# LTC_Hardware.net
KiCad netlist of a schematic drawn in Altium Designer
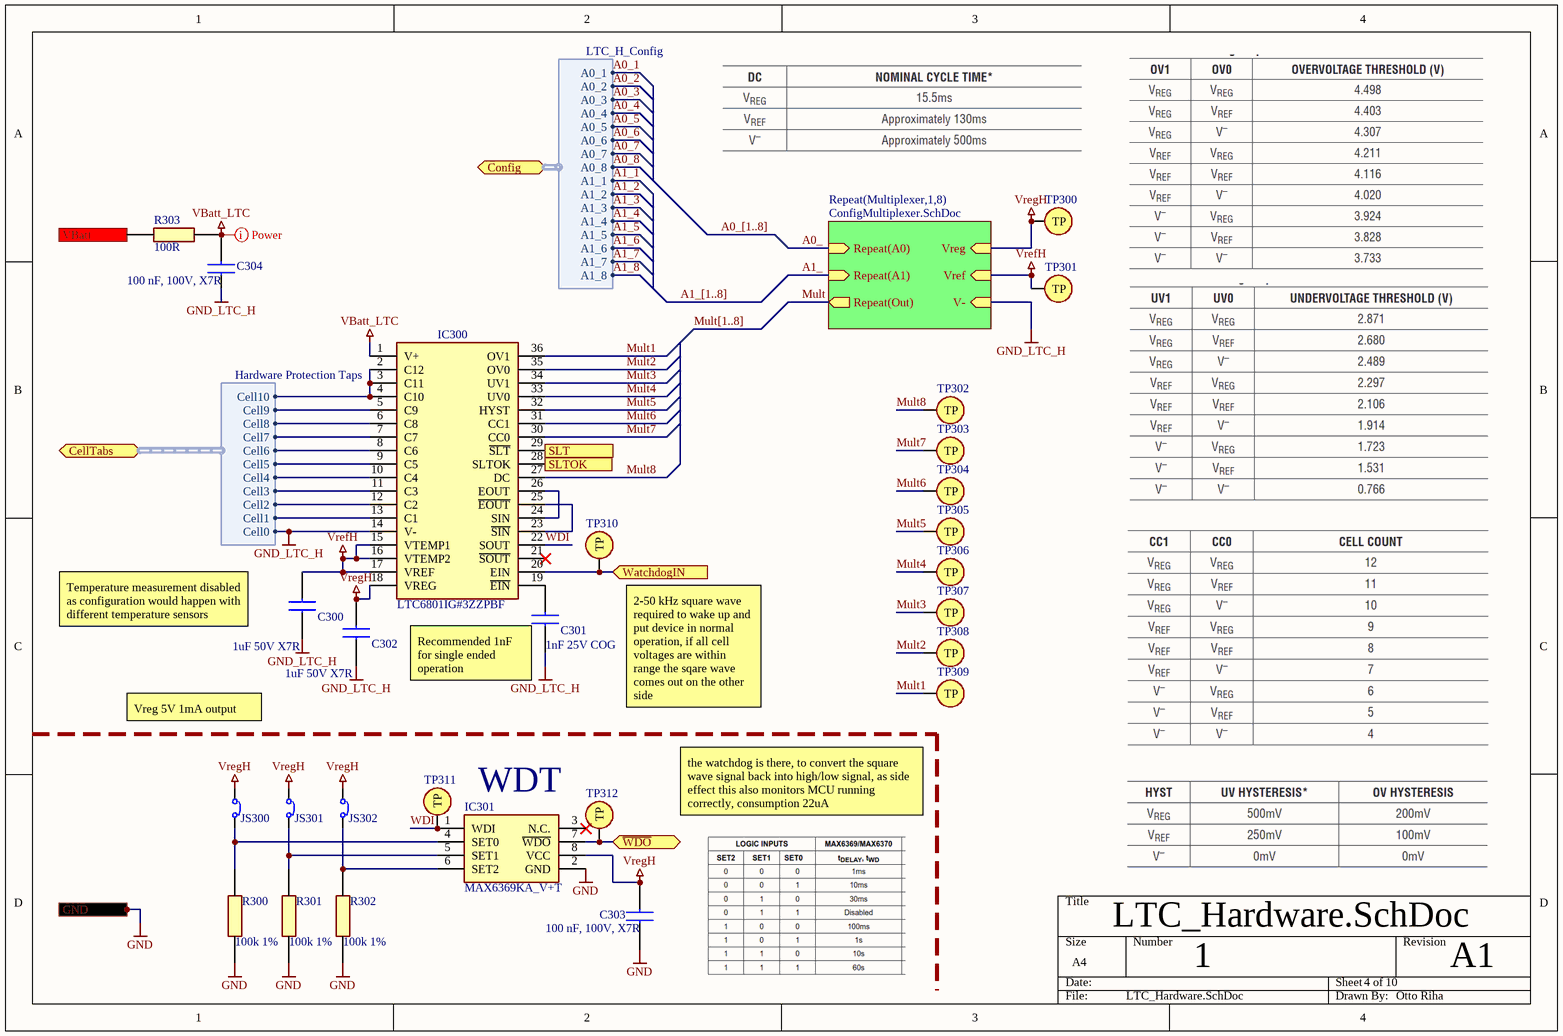
[diagram p0: LTC_Hardware.SchDoc]

(export (version "E")
  (design (tool "Eeschema 10.0.6"))
  (components
    (comp (ref "C300")
      (value "1uF 50V X7R")
      (footprint "SamacSys:CAPC1608X90N")
      (description "Capacitor 1uF 50V X7R")
      (fields
        (field (name "MANUFACTURER_PART_NUMBER") "06035C105MAT2A")
        (field (name "MOUSER PART NUMBER") "581-06035C105MAT2A")
      )
      (libsource (lib "SamacSys") (part "06035C105MAT2A"))
    )
    (comp (ref "C301")
      (value "1nF 25V COG")
      (footprint "SamacSys:CAPC1608X90N")
      (description "Capacitor 1nF 25V COG")
      (fields
        (field (name "MANUFACTURER_PART_NUMBER") "06033A102FAT2A")
        (field (name "MOUSER PART NUMBER") "581-06033A102F")
      )
      (libsource (lib "SamacSys") (part "06033A102FAT2A"))
    )
    (comp (ref "C302")
      (value "1uF 50V X7R")
      (footprint "SamacSys:CAPC1608X90N")
      (description "Capacitor 1uF 50V X7R")
      (fields
        (field (name "MANUFACTURER_PART_NUMBER") "06035C105MAT2A")
        (field (name "MOUSER PART NUMBER") "581-06035C105MAT2A")
      )
      (libsource (lib "SamacSys") (part "06035C105MAT2A"))
    )
    (comp (ref "C303")
      (value "100 nF, 100V, X7R")
      (footprint "SamacSys:MAJx16")
      (description "Capacitor 100nF, 100V, X7R")
      (fields
        (field (name "MANUFACTURER_PART_NUMBER") "MAJCH168BB7104KTEA01")
        (field (name "MOUSER PART NUMBER") "963-MAJCH168BB7104KT")
      )
      (libsource (lib "SamacSys") (part "MAJCH168BB7104KTEA01"))
    )
    (comp (ref "C304")
      (value "100 nF, 100V, X7R")
      (footprint "SamacSys:MAJx16")
      (description "Capacitor 100nF, 100V, X7R")
      (fields
        (field (name "MANUFACTURER_PART_NUMBER") "MAJCH168BB7104KTEA01")
        (field (name "MOUSER PART NUMBER") "963-MAJCH168BB7104KT")
      )
      (libsource (lib "SamacSys") (part "MAJCH168BB7104KTEA01"))
    )
    (comp (ref "IC300")
      (value "LTC6801IG#3ZZPBF")
      (footprint "SamacSys:SOP65P780X200-36N")
      (description "Integrated Circuit")
      (fields (field (name "MOUSER PART NUMBER") "584-LTC6801IG#3ZZPBF"))
      (libsource (lib "*") (part "LTC6801IG#3ZZPBF"))
    )
    (comp (ref "IC301")
      (value "MAX6369KA_V+T")
      (footprint "SamacSys:SOT65P280X145-8N")
      (description "Integrated Circuit")
      (fields
        (field (name "MANUFACTURER_PART_NUMBER") "MAX6369KA/V+T")
        (field (name "MOUSER PART NUMBER") "700-MAX6369KA/V+T")
      )
      (libsource (lib "SamacSys") (part "MAX6369KA_V+T"))
    )
    (comp (ref "JS300")
      (value "SolderJumper")
      (footprint "SolderJumper")
      (libsource (lib "SamacSys") (part "SolderJumper"))
    )
    (comp (ref "JS301")
      (value "SolderJumper")
      (footprint "SolderJumper")
      (libsource (lib "SamacSys") (part "SolderJumper"))
    )
    (comp (ref "JS302")
      (value "SolderJumper")
      (footprint "SolderJumper")
      (libsource (lib "SamacSys") (part "SolderJumper"))
    )
    (comp (ref "R300")
      (value "100k 1%")
      (footprint "SamacSys:RESC1608X55N")
      (description "Resistor 100k, 1%")
      (fields
        (field (name "MANUFACTURER_PART_NUMBER") "CRCW0603100KFKEAC")
        (field (name "MOUSER PART NUMBER") "71-CRCW0603100KFKEAC")
      )
      (libsource (lib "SamacSys") (part "CRCW0603100KFKEAC"))
    )
    (comp (ref "R301")
      (value "100k 1%")
      (footprint "SamacSys:RESC1608X55N")
      (description "Resistor 100k, 1%")
      (fields
        (field (name "MANUFACTURER_PART_NUMBER") "CRCW0603100KFKEAC")
        (field (name "MOUSER PART NUMBER") "71-CRCW0603100KFKEAC")
      )
      (libsource (lib "SamacSys") (part "CRCW0603100KFKEAC"))
    )
    (comp (ref "R302")
      (value "100k 1%")
      (footprint "SamacSys:RESC1608X55N")
      (description "Resistor 100k, 1%")
      (fields
        (field (name "MANUFACTURER_PART_NUMBER") "CRCW0603100KFKEAC")
        (field (name "MOUSER PART NUMBER") "71-CRCW0603100KFKEAC")
      )
      (libsource (lib "SamacSys") (part "CRCW0603100KFKEAC"))
    )
    (comp (ref "R303")
      (value "100R")
      (footprint "SamacSys:RESC1608X50N")
      (description "Resistor 100R, 1%")
      (fields
        (field (name "MANUFACTURER_PART_NUMBER") "CRCW0603100RFKEA")
        (field (name "MOUSER PART NUMBER") "71-CRCW0603-100-E3")
      )
      (libsource (lib "SamacSys") (part "CRCW0603100RFKEA"))
    )
    (comp (ref "TP300")
      (value "Testpoint")
      (footprint "Testpoint")
      (libsource (lib "SamacSys") (part "Testpoint"))
    )
    (comp (ref "TP301")
      (value "Testpoint")
      (footprint "Testpoint")
      (libsource (lib "SamacSys") (part "Testpoint"))
    )
    (comp (ref "TP302")
      (value "Testpoint")
      (footprint "Testpoint")
      (libsource (lib "SamacSys") (part "Testpoint"))
    )
    (comp (ref "TP303")
      (value "Testpoint")
      (footprint "Testpoint")
      (libsource (lib "SamacSys") (part "Testpoint"))
    )
    (comp (ref "TP304")
      (value "Testpoint")
      (footprint "Testpoint")
      (libsource (lib "SamacSys") (part "Testpoint"))
    )
    (comp (ref "TP305")
      (value "Testpoint")
      (footprint "Testpoint")
      (libsource (lib "SamacSys") (part "Testpoint"))
    )
    (comp (ref "TP306")
      (value "Testpoint")
      (footprint "Testpoint")
      (libsource (lib "SamacSys") (part "Testpoint"))
    )
    (comp (ref "TP307")
      (value "Testpoint")
      (footprint "Testpoint")
      (libsource (lib "SamacSys") (part "Testpoint"))
    )
    (comp (ref "TP308")
      (value "Testpoint")
      (footprint "Testpoint")
      (libsource (lib "SamacSys") (part "Testpoint"))
    )
    (comp (ref "TP309")
      (value "Testpoint")
      (footprint "Testpoint")
      (libsource (lib "SamacSys") (part "Testpoint"))
    )
    (comp (ref "TP310")
      (value "Testpoint")
      (footprint "Testpoint")
      (libsource (lib "SamacSys") (part "Testpoint"))
    )
    (comp (ref "TP311")
      (value "Testpoint")
      (footprint "Testpoint")
      (libsource (lib "SamacSys") (part "Testpoint"))
    )
    (comp (ref "TP312")
      (value "Testpoint")
      (footprint "Testpoint")
      (libsource (lib "SamacSys") (part "Testpoint"))
    )
  )
  (nets
    (net (code "25") (name "/Cell1") (class "Default")
      (node (ref "IC300") (pin "13") (pinfunction "C1_13") (pintype "passive"))
    )
    (net (code "26") (name "/Cell2") (class "Default")
      (node (ref "IC300") (pin "12") (pinfunction "C2_12") (pintype "passive"))
    )
    (net (code "27") (name "/Cell3") (class "Default")
      (node (ref "IC300") (pin "11") (pinfunction "C3_11") (pintype "passive"))
    )
    (net (code "28") (name "/Cell4") (class "Default")
      (node (ref "IC300") (pin "10") (pinfunction "C4_10") (pintype "passive"))
    )
    (net (code "29") (name "/Cell5") (class "Default")
      (node (ref "IC300") (pin "9") (pinfunction "C5_9") (pintype "passive"))
    )
    (net (code "30") (name "/Cell6") (class "Default")
      (node (ref "IC300") (pin "8") (pinfunction "C6_8") (pintype "passive"))
    )
    (net (code "31") (name "/Cell7") (class "Default")
      (node (ref "IC300") (pin "7") (pinfunction "C7_7") (pintype "passive"))
    )
    (net (code "32") (name "/Cell8") (class "Default")
      (node (ref "IC300") (pin "6") (pinfunction "C8_6") (pintype "passive"))
    )
    (net (code "33") (name "/Cell9") (class "Default")
      (node (ref "IC300") (pin "5") (pinfunction "C9_5") (pintype "passive"))
    )
    (net (code "34") (name "/Cell10") (class "Default")
      (node (ref "IC300") (pin "2") (pinfunction "C12_2") (pintype "passive"))
      (node (ref "IC300") (pin "3") (pinfunction "C11_3") (pintype "passive"))
      (node (ref "IC300") (pin "4") (pinfunction "C10_4") (pintype "passive"))
    )
    (net (code "36") (name "/Mult1") (class "Default")
      (node (ref "IC300") (pin "36") (pinfunction "OV1_36") (pintype "passive"))
      (node (ref "TP309") (pin "1") (pinfunction "TP_1") (pintype "passive"))
    )
    (net (code "37") (name "/Mult2") (class "Default")
      (node (ref "IC300") (pin "35") (pinfunction "OV0_35") (pintype "passive"))
      (node (ref "TP308") (pin "1") (pinfunction "TP_1") (pintype "passive"))
    )
    (net (code "38") (name "/Mult3") (class "Default")
      (node (ref "IC300") (pin "34") (pinfunction "UV1_34") (pintype "passive"))
      (node (ref "TP307") (pin "1") (pinfunction "TP_1") (pintype "passive"))
    )
    (net (code "39") (name "/Mult4") (class "Default")
      (node (ref "IC300") (pin "33") (pinfunction "UV0_33") (pintype "passive"))
      (node (ref "TP306") (pin "1") (pinfunction "TP_1") (pintype "passive"))
    )
    (net (code "40") (name "/Mult5") (class "Default")
      (node (ref "IC300") (pin "32") (pinfunction "HYST_32") (pintype "passive"))
      (node (ref "TP305") (pin "1") (pinfunction "TP_1") (pintype "passive"))
    )
    (net (code "41") (name "/Mult6") (class "Default")
      (node (ref "IC300") (pin "31") (pinfunction "CC1_31") (pintype "passive"))
      (node (ref "TP304") (pin "1") (pinfunction "TP_1") (pintype "passive"))
    )
    (net (code "42") (name "/Mult7") (class "Default")
      (node (ref "IC300") (pin "30") (pinfunction "CC0_30") (pintype "passive"))
      (node (ref "TP303") (pin "1") (pinfunction "TP_1") (pintype "passive"))
    )
    (net (code "43") (name "/Mult8") (class "Default")
      (node (ref "IC300") (pin "27") (pinfunction "DC_27") (pintype "passive"))
      (node (ref "TP302") (pin "1") (pinfunction "TP_1") (pintype "passive"))
    )
    (net (code "45") (name "/SLT") (class "Default")
      (node (ref "IC300") (pin "29") (pinfunction "~{SLT}_29") (pintype "passive"))
    )
    (net (code "46") (name "/SLTOK") (class "Default")
      (node (ref "IC300") (pin "28") (pinfunction "SLTOK_28") (pintype "passive"))
    )
    (net (code "47") (name "/VBatt") (class "Default")
      (node (ref "R303") (pin "1") (pinfunction "1_1") (pintype "passive"))
    )
    (net (code "48") (name "/WDI") (class "Default")
      (node (ref "IC300") (pin "22") (pinfunction "SOUT_22") (pintype "passive"))
      (node (ref "IC301") (pin "1") (pinfunction "WDI_1") (pintype "passive"))
      (node (ref "TP311") (pin "1") (pinfunction "TP_1") (pintype "passive"))
    )
    (net (code "49") (name "/WatchdogIN") (class "Default")
      (node (ref "IC300") (pin "20") (pinfunction "EIN_20") (pintype "passive"))
      (node (ref "TP310") (pin "1") (pinfunction "TP_1") (pintype "passive"))
    )
    (net (code "52") (name "/~{WDO}") (class "Default")
      (node (ref "IC301") (pin "7") (pinfunction "~{WDO}_7") (pintype "passive"))
      (node (ref "TP312") (pin "1") (pinfunction "TP_1") (pintype "passive"))
    )
    (net (code "53") (name "GND") (class "Default")
      (node (ref "C303") (pin "1") (pinfunction "1_1") (pintype "passive"))
      (node (ref "IC301") (pin "2") (pinfunction "GND_2") (pintype "power_in"))
      (node (ref "R300") (pin "1") (pinfunction "1_1") (pintype "passive"))
      (node (ref "R301") (pin "1") (pinfunction "1_1") (pintype "passive"))
      (node (ref "R302") (pin "1") (pinfunction "1_1") (pintype "passive"))
    )
    (net (code "54") (name "GND_LTC_H") (class "Default")
      (node (ref "C300") (pin "2") (pinfunction "2_2") (pintype "passive"))
      (node (ref "C301") (pin "1") (pinfunction "1_1") (pintype "passive"))
      (node (ref "C302") (pin "2") (pinfunction "2_2") (pintype "passive"))
      (node (ref "C304") (pin "1") (pinfunction "1_1") (pintype "passive"))
      (node (ref "IC300") (pin "14") (pinfunction "V-_14") (pintype "passive"))
    )
    (net (code "55") (name "Net-(IC300-EOUT)") (class "Default")
      (node (ref "IC300") (pin "24") (pinfunction "SIN_24") (pintype "passive"))
      (node (ref "IC300") (pin "26") (pinfunction "EOUT_26") (pintype "passive"))
    )
    (net (code "56") (name "Net-(IC300-~{EIN})") (class "Default")
      (node (ref "C301") (pin "2") (pinfunction "2_2") (pintype "passive"))
      (node (ref "IC300") (pin "19") (pinfunction "~{EIN}_19") (pintype "passive"))
    )
    (net (code "57") (name "Net-(IC300-~{EOUT})") (class "Default")
      (node (ref "IC300") (pin "23") (pinfunction "~{SIN}_23") (pintype "passive"))
      (node (ref "IC300") (pin "25") (pinfunction "~{EOUT}_25") (pintype "passive"))
    )
    (net (code "58") (name "Net-(IC301-SET0)") (class "Default")
      (node (ref "IC301") (pin "4") (pinfunction "SET0_4") (pintype "passive"))
      (node (ref "JS300") (pin "1") (pinfunction "1_1") (pintype "passive"))
      (node (ref "R300") (pin "2") (pinfunction "2_2") (pintype "passive"))
    )
    (net (code "59") (name "Net-(IC301-SET1)") (class "Default")
      (node (ref "IC301") (pin "5") (pinfunction "SET1_5") (pintype "passive"))
      (node (ref "JS301") (pin "1") (pinfunction "1_1") (pintype "passive"))
      (node (ref "R301") (pin "2") (pinfunction "2_2") (pintype "passive"))
    )
    (net (code "60") (name "Net-(IC301-SET2)") (class "Default")
      (node (ref "IC301") (pin "6") (pinfunction "SET2_6") (pintype "passive"))
      (node (ref "JS302") (pin "1") (pinfunction "1_1") (pintype "passive"))
      (node (ref "R302") (pin "2") (pinfunction "2_2") (pintype "passive"))
    )
    (net (code "61") (name "VBatt_LTC") (class "Default")
      (node (ref "C304") (pin "2") (pinfunction "2_2") (pintype "passive"))
      (node (ref "IC300") (pin "1") (pinfunction "V+_1") (pintype "passive"))
      (node (ref "R303") (pin "2") (pinfunction "2_2") (pintype "passive"))
    )
    (net (code "62") (name "VrefH") (class "Default")
      (node (ref "C300") (pin "1") (pinfunction "1_1") (pintype "passive"))
      (node (ref "IC300") (pin "15") (pinfunction "VTEMP1_15") (pintype "passive"))
      (node (ref "IC300") (pin "16") (pinfunction "VTEMP2_16") (pintype "passive"))
      (node (ref "IC300") (pin "17") (pinfunction "VREF_17") (pintype "passive"))
      (node (ref "TP301") (pin "1") (pinfunction "TP_1") (pintype "passive"))
    )
    (net (code "63") (name "VregH") (class "Default")
      (node (ref "C302") (pin "1") (pinfunction "1_1") (pintype "passive"))
      (node (ref "C303") (pin "2") (pinfunction "2_2") (pintype "passive"))
      (node (ref "IC300") (pin "18") (pinfunction "VREG_18") (pintype "passive"))
      (node (ref "IC301") (pin "8") (pinfunction "VCC_8") (pintype "power_in"))
      (node (ref "JS300") (pin "2") (pinfunction "2_2") (pintype "passive"))
      (node (ref "JS301") (pin "2") (pinfunction "2_2") (pintype "passive"))
      (node (ref "JS302") (pin "2") (pinfunction "2_2") (pintype "passive"))
      (node (ref "TP300") (pin "1") (pinfunction "TP_1") (pintype "passive"))
    )
    (net (code "64") (name "unconnected-(IC300-~{SOUT}-Pad21)") (class "Default")
      (node (ref "IC300") (pin "21") (pinfunction "~{SOUT}_21") (pintype "passive+no_connect"))
    )
    (net (code "65") (name "unconnected-(IC301-N.C.-Pad3)") (class "Default")
      (node (ref "IC301") (pin "3") (pinfunction "N.C._3") (pintype "passive+no_connect"))
    )
  )
)
